# Empty_Shield_SMD-v13.net
KiCad netlist of a schematic drawn in EAGLE
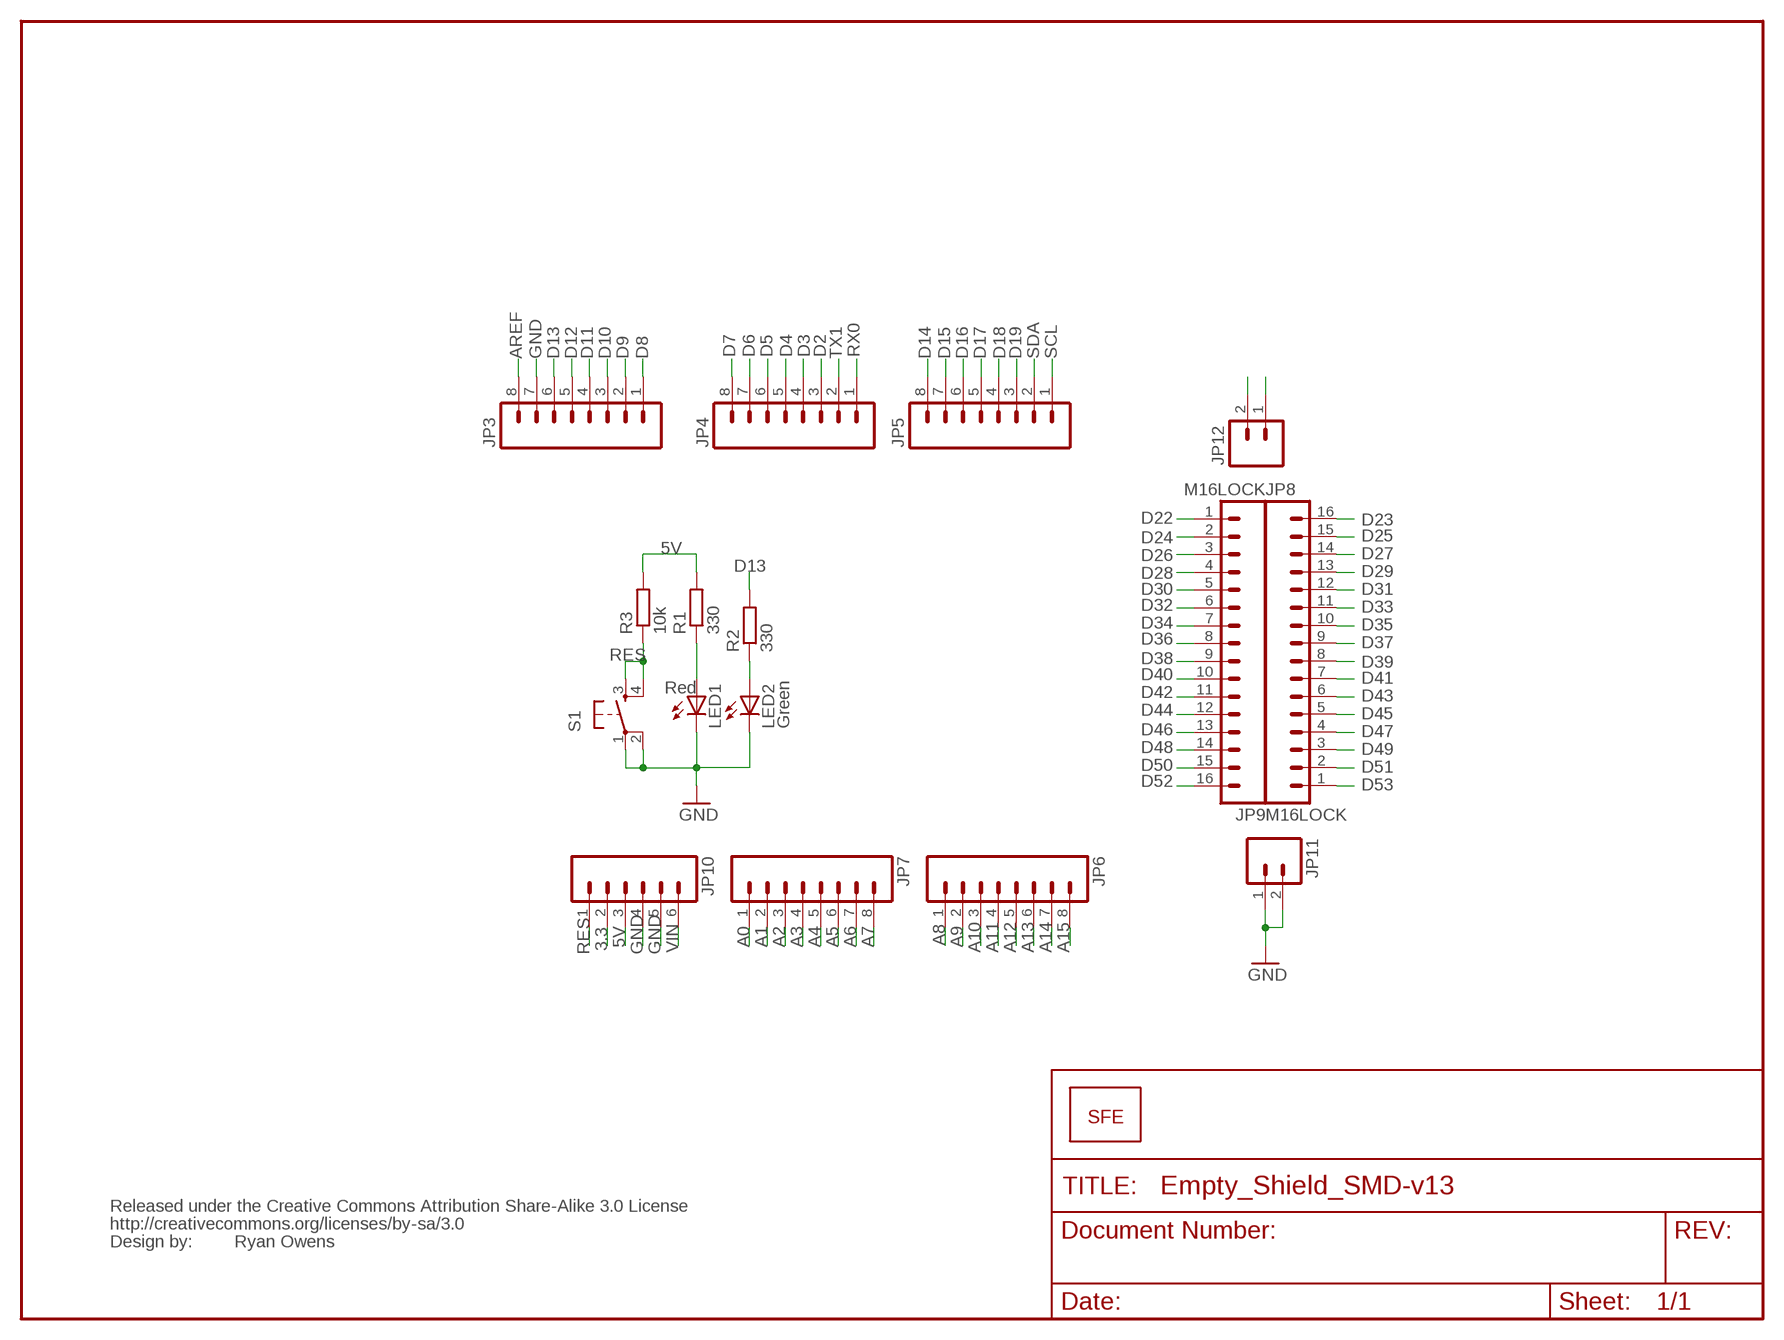
[diagram p0: schematic, sheet 1]

(export (version "E")
  (design (tool "Eeschema 10.0.6"))
  (components
    (comp (ref "JP3")
      (value "M08LOCK")
      (footprint "eagle-import:1X08_LOCK")
      (libsource (lib "eagle-import") (part "M08LOCK"))
    )
    (comp (ref "JP4")
      (value "M08LOCK")
      (footprint "eagle-import:1X08_LOCK")
      (libsource (lib "eagle-import") (part "M08LOCK"))
    )
    (comp (ref "JP5")
      (value "M08LOCK")
      (footprint "eagle-import:1X08_LOCK")
      (libsource (lib "eagle-import") (part "M08LOCK"))
    )
    (comp (ref "JP6")
      (value "M08LOCK")
      (footprint "eagle-import:1X08_LOCK")
      (libsource (lib "eagle-import") (part "M08LOCK"))
    )
    (comp (ref "JP7")
      (value "M08LOCK")
      (footprint "eagle-import:1X08_LOCK")
      (libsource (lib "eagle-import") (part "M08LOCK"))
    )
    (comp (ref "JP8")
      (value "M16LOCK")
      (footprint "eagle-import:1X16_LOCK")
      (libsource (lib "eagle-import") (part "M16LOCK"))
    )
    (comp (ref "JP9")
      (value "M16LOCK")
      (footprint "eagle-import:1X16_LOCK")
      (libsource (lib "eagle-import") (part "M16LOCK"))
    )
    (comp (ref "JP10")
      (value "M06LOCK")
      (footprint "eagle-import:1X06_LOCK")
      (libsource (lib "eagle-import") (part "M06LOCK"))
    )
    (comp (ref "JP11")
      (value "M02LOCK")
      (footprint "eagle-import:1X02_LOCK")
      (libsource (lib "eagle-import") (part "M02LOCK"))
    )
    (comp (ref "JP12")
      (value "M02LOCK")
      (footprint "eagle-import:1X02_LOCK")
      (libsource (lib "eagle-import") (part "M02LOCK"))
    )
    (comp (ref "LED1")
      (value "Red")
      (footprint "eagle-import:CHIP-LED0805")
      (libsource (lib "eagle-import") (part "LEDCHIP-LED0805"))
    )
    (comp (ref "LED2")
      (value "Green")
      (footprint "eagle-import:CHIP-LED0805")
      (libsource (lib "eagle-import") (part "LEDCHIP-LED0805"))
    )
    (comp (ref "R1")
      (value "330")
      (footprint "eagle-import:R0805")
      (libsource (lib "eagle-import") (part "R-EU_R0805"))
    )
    (comp (ref "R2")
      (value "330")
      (footprint "eagle-import:R0805")
      (libsource (lib "eagle-import") (part "R-EU_R0805"))
    )
    (comp (ref "R3")
      (value "10k")
      (footprint "eagle-import:R0805")
      (libsource (lib "eagle-import") (part "R-EU_R0805"))
    )
    (comp (ref "S1")
      (value "TAC_SWITCHPTH")
      (footprint "eagle-import:TACTILE-PTH")
      (libsource (lib "eagle-import") (part "TAC_SWITCHPTH"))
    )
    (comp (ref "U$1")
      (value "LOGO-SFENEW")
      (footprint "eagle-import:SFE-NEW-WEBLOGO")
      (libsource (lib "eagle-import") (part "LOGO-SFENEW"))
    )
    (comp (ref "U$2")
      (value "CREATIVE_COMMONS")
      (footprint "eagle-import:CREATIVE_COMMONS")
      (libsource (lib "eagle-import") (part "CREATIVE_COMMONS"))
    )
  )
  (nets
    (net (code "1") (name "/3.3") (class "Default")
      (node (ref "JP10") (pin "2") (pinfunction "2_2") (pintype "passive"))
    )
    (net (code "2") (name "/5V") (class "Default")
      (node (ref "JP10") (pin "3") (pinfunction "3_3") (pintype "passive"))
      (node (ref "R1") (pin "2") (pinfunction "2_2") (pintype "passive"))
      (node (ref "R3") (pin "2") (pinfunction "2_2") (pintype "passive"))
    )
    (net (code "3") (name "/5V@1") (class "Default")
      (node (ref "JP12") (pin "1") (pinfunction "1_1") (pintype "passive"))
      (node (ref "JP12") (pin "2") (pinfunction "2_2") (pintype "passive"))
    )
    (net (code "4") (name "/A0") (class "Default")
      (node (ref "JP7") (pin "1") (pinfunction "1_1") (pintype "passive"))
    )
    (net (code "5") (name "/A1") (class "Default")
      (node (ref "JP7") (pin "2") (pinfunction "2_2") (pintype "passive"))
    )
    (net (code "6") (name "/A2") (class "Default")
      (node (ref "JP7") (pin "3") (pinfunction "3_3") (pintype "passive"))
    )
    (net (code "7") (name "/A3") (class "Default")
      (node (ref "JP7") (pin "4") (pinfunction "4_4") (pintype "passive"))
    )
    (net (code "8") (name "/A4") (class "Default")
      (node (ref "JP7") (pin "5") (pinfunction "5_5") (pintype "passive"))
    )
    (net (code "9") (name "/A5") (class "Default")
      (node (ref "JP7") (pin "6") (pinfunction "6_6") (pintype "passive"))
    )
    (net (code "10") (name "/A6") (class "Default")
      (node (ref "JP7") (pin "7") (pinfunction "7_7") (pintype "passive"))
    )
    (net (code "11") (name "/A7") (class "Default")
      (node (ref "JP7") (pin "8") (pinfunction "8_8") (pintype "passive"))
    )
    (net (code "12") (name "/A8") (class "Default")
      (node (ref "JP6") (pin "1") (pinfunction "1_1") (pintype "passive"))
    )
    (net (code "13") (name "/A9") (class "Default")
      (node (ref "JP6") (pin "2") (pinfunction "2_2") (pintype "passive"))
    )
    (net (code "14") (name "/A10") (class "Default")
      (node (ref "JP6") (pin "3") (pinfunction "3_3") (pintype "passive"))
    )
    (net (code "15") (name "/A11") (class "Default")
      (node (ref "JP6") (pin "4") (pinfunction "4_4") (pintype "passive"))
    )
    (net (code "16") (name "/A12") (class "Default")
      (node (ref "JP6") (pin "5") (pinfunction "5_5") (pintype "passive"))
    )
    (net (code "17") (name "/A13") (class "Default")
      (node (ref "JP6") (pin "6") (pinfunction "6_6") (pintype "passive"))
    )
    (net (code "18") (name "/A14") (class "Default")
      (node (ref "JP6") (pin "7") (pinfunction "7_7") (pintype "passive"))
    )
    (net (code "19") (name "/A15") (class "Default")
      (node (ref "JP6") (pin "8") (pinfunction "8_8") (pintype "passive"))
    )
    (net (code "20") (name "/AREF") (class "Default")
      (node (ref "JP3") (pin "8") (pinfunction "8_8") (pintype "passive"))
    )
    (net (code "21") (name "/D2") (class "Default")
      (node (ref "JP4") (pin "3") (pinfunction "3_3") (pintype "passive"))
    )
    (net (code "22") (name "/D3") (class "Default")
      (node (ref "JP4") (pin "4") (pinfunction "4_4") (pintype "passive"))
    )
    (net (code "23") (name "/D4") (class "Default")
      (node (ref "JP4") (pin "5") (pinfunction "5_5") (pintype "passive"))
    )
    (net (code "24") (name "/D5") (class "Default")
      (node (ref "JP4") (pin "6") (pinfunction "6_6") (pintype "passive"))
    )
    (net (code "25") (name "/D6") (class "Default")
      (node (ref "JP4") (pin "7") (pinfunction "7_7") (pintype "passive"))
    )
    (net (code "26") (name "/D7") (class "Default")
      (node (ref "JP4") (pin "8") (pinfunction "8_8") (pintype "passive"))
    )
    (net (code "27") (name "/D8") (class "Default")
      (node (ref "JP3") (pin "1") (pinfunction "1_1") (pintype "passive"))
    )
    (net (code "28") (name "/D9") (class "Default")
      (node (ref "JP3") (pin "2") (pinfunction "2_2") (pintype "passive"))
    )
    (net (code "29") (name "/D10") (class "Default")
      (node (ref "JP3") (pin "3") (pinfunction "3_3") (pintype "passive"))
    )
    (net (code "30") (name "/D11") (class "Default")
      (node (ref "JP3") (pin "4") (pinfunction "4_4") (pintype "passive"))
    )
    (net (code "31") (name "/D12") (class "Default")
      (node (ref "JP3") (pin "5") (pinfunction "5_5") (pintype "passive"))
    )
    (net (code "32") (name "/D13") (class "Default")
      (node (ref "JP3") (pin "6") (pinfunction "6_6") (pintype "passive"))
      (node (ref "R2") (pin "2") (pinfunction "2_2") (pintype "passive"))
    )
    (net (code "33") (name "/D14") (class "Default")
      (node (ref "JP5") (pin "8") (pinfunction "8_8") (pintype "passive"))
    )
    (net (code "34") (name "/D15") (class "Default")
      (node (ref "JP5") (pin "7") (pinfunction "7_7") (pintype "passive"))
    )
    (net (code "35") (name "/D16") (class "Default")
      (node (ref "JP5") (pin "6") (pinfunction "6_6") (pintype "passive"))
    )
    (net (code "36") (name "/D17") (class "Default")
      (node (ref "JP5") (pin "5") (pinfunction "5_5") (pintype "passive"))
    )
    (net (code "37") (name "/D18") (class "Default")
      (node (ref "JP5") (pin "4") (pinfunction "4_4") (pintype "passive"))
    )
    (net (code "38") (name "/D19") (class "Default")
      (node (ref "JP5") (pin "3") (pinfunction "3_3") (pintype "passive"))
    )
    (net (code "39") (name "/D22") (class "Default")
      (node (ref "JP9") (pin "1") (pinfunction "1_1") (pintype "passive"))
    )
    (net (code "40") (name "/D23") (class "Default")
      (node (ref "JP8") (pin "16") (pinfunction "16_16") (pintype "passive"))
    )
    (net (code "41") (name "/D24") (class "Default")
      (node (ref "JP9") (pin "2") (pinfunction "2_2") (pintype "passive"))
    )
    (net (code "42") (name "/D25") (class "Default")
      (node (ref "JP8") (pin "15") (pinfunction "15_15") (pintype "passive"))
    )
    (net (code "43") (name "/D26") (class "Default")
      (node (ref "JP9") (pin "3") (pinfunction "3_3") (pintype "passive"))
    )
    (net (code "44") (name "/D27") (class "Default")
      (node (ref "JP8") (pin "14") (pinfunction "14_14") (pintype "passive"))
    )
    (net (code "45") (name "/D28") (class "Default")
      (node (ref "JP9") (pin "4") (pinfunction "4_4") (pintype "passive"))
    )
    (net (code "46") (name "/D29") (class "Default")
      (node (ref "JP8") (pin "13") (pinfunction "13_13") (pintype "passive"))
    )
    (net (code "47") (name "/D30") (class "Default")
      (node (ref "JP9") (pin "5") (pinfunction "5_5") (pintype "passive"))
    )
    (net (code "48") (name "/D31") (class "Default")
      (node (ref "JP8") (pin "12") (pinfunction "12_12") (pintype "passive"))
    )
    (net (code "49") (name "/D32") (class "Default")
      (node (ref "JP9") (pin "6") (pinfunction "6_6") (pintype "passive"))
    )
    (net (code "50") (name "/D33") (class "Default")
      (node (ref "JP8") (pin "11") (pinfunction "11_11") (pintype "passive"))
    )
    (net (code "51") (name "/D34") (class "Default")
      (node (ref "JP9") (pin "7") (pinfunction "7_7") (pintype "passive"))
    )
    (net (code "52") (name "/D35") (class "Default")
      (node (ref "JP8") (pin "10") (pinfunction "10_10") (pintype "passive"))
    )
    (net (code "53") (name "/D36") (class "Default")
      (node (ref "JP9") (pin "8") (pinfunction "8_8") (pintype "passive"))
    )
    (net (code "54") (name "/D37") (class "Default")
      (node (ref "JP8") (pin "9") (pinfunction "9_9") (pintype "passive"))
    )
    (net (code "55") (name "/D38") (class "Default")
      (node (ref "JP9") (pin "9") (pinfunction "9_9") (pintype "passive"))
    )
    (net (code "56") (name "/D39") (class "Default")
      (node (ref "JP8") (pin "8") (pinfunction "8_8") (pintype "passive"))
    )
    (net (code "57") (name "/D40") (class "Default")
      (node (ref "JP9") (pin "10") (pinfunction "10_10") (pintype "passive"))
    )
    (net (code "58") (name "/D41") (class "Default")
      (node (ref "JP8") (pin "7") (pinfunction "7_7") (pintype "passive"))
    )
    (net (code "59") (name "/D42") (class "Default")
      (node (ref "JP9") (pin "11") (pinfunction "11_11") (pintype "passive"))
    )
    (net (code "60") (name "/D43") (class "Default")
      (node (ref "JP8") (pin "6") (pinfunction "6_6") (pintype "passive"))
    )
    (net (code "61") (name "/D44") (class "Default")
      (node (ref "JP9") (pin "12") (pinfunction "12_12") (pintype "passive"))
    )
    (net (code "62") (name "/D45") (class "Default")
      (node (ref "JP8") (pin "5") (pinfunction "5_5") (pintype "passive"))
    )
    (net (code "63") (name "/D46") (class "Default")
      (node (ref "JP9") (pin "13") (pinfunction "13_13") (pintype "passive"))
    )
    (net (code "64") (name "/D47") (class "Default")
      (node (ref "JP8") (pin "4") (pinfunction "4_4") (pintype "passive"))
    )
    (net (code "65") (name "/D48") (class "Default")
      (node (ref "JP9") (pin "14") (pinfunction "14_14") (pintype "passive"))
    )
    (net (code "66") (name "/D49") (class "Default")
      (node (ref "JP8") (pin "3") (pinfunction "3_3") (pintype "passive"))
    )
    (net (code "67") (name "/D50") (class "Default")
      (node (ref "JP9") (pin "15") (pinfunction "15_15") (pintype "passive"))
    )
    (net (code "68") (name "/D51") (class "Default")
      (node (ref "JP8") (pin "2") (pinfunction "2_2") (pintype "passive"))
    )
    (net (code "69") (name "/D52") (class "Default")
      (node (ref "JP9") (pin "16") (pinfunction "16_16") (pintype "passive"))
    )
    (net (code "70") (name "/D53") (class "Default")
      (node (ref "JP8") (pin "1") (pinfunction "1_1") (pintype "passive"))
    )
    (net (code "71") (name "/RES") (class "Default")
      (node (ref "JP10") (pin "1") (pinfunction "1_1") (pintype "passive"))
      (node (ref "R3") (pin "1") (pinfunction "1_1") (pintype "passive"))
      (node (ref "S1") (pin "3") (pinfunction "3_3") (pintype "passive"))
      (node (ref "S1") (pin "4") (pinfunction "4_4") (pintype "passive"))
    )
    (net (code "72") (name "/RX0") (class "Default")
      (node (ref "JP4") (pin "1") (pinfunction "1_1") (pintype "passive"))
    )
    (net (code "73") (name "/SCL") (class "Default")
      (node (ref "JP5") (pin "1") (pinfunction "1_1") (pintype "passive"))
    )
    (net (code "74") (name "/SDA") (class "Default")
      (node (ref "JP5") (pin "2") (pinfunction "2_2") (pintype "passive"))
    )
    (net (code "75") (name "/TX1") (class "Default")
      (node (ref "JP4") (pin "2") (pinfunction "2_2") (pintype "passive"))
    )
    (net (code "76") (name "/VIN") (class "Default")
      (node (ref "JP10") (pin "6") (pinfunction "6_6") (pintype "passive"))
    )
    (net (code "77") (name "GND") (class "Default")
      (node (ref "JP10") (pin "4") (pinfunction "4_4") (pintype "passive"))
      (node (ref "JP10") (pin "5") (pinfunction "5_5") (pintype "passive"))
      (node (ref "JP11") (pin "1") (pinfunction "1_1") (pintype "passive"))
      (node (ref "JP11") (pin "2") (pinfunction "2_2") (pintype "passive"))
      (node (ref "JP3") (pin "7") (pinfunction "7_7") (pintype "passive"))
      (node (ref "LED1") (pin "C") (pinfunction "C_C") (pintype "passive"))
      (node (ref "LED2") (pin "C") (pinfunction "C_C") (pintype "passive"))
      (node (ref "S1") (pin "1") (pinfunction "1_1") (pintype "passive"))
      (node (ref "S1") (pin "2") (pinfunction "2_2") (pintype "passive"))
    )
    (net (code "78") (name "Net-(LED1-PadA)") (class "Default")
      (node (ref "LED1") (pin "A") (pinfunction "A_A") (pintype "passive"))
      (node (ref "R1") (pin "1") (pinfunction "1_1") (pintype "passive"))
    )
    (net (code "79") (name "Net-(LED2-PadA)") (class "Default")
      (node (ref "LED2") (pin "A") (pinfunction "A_A") (pintype "passive"))
      (node (ref "R2") (pin "1") (pinfunction "1_1") (pintype "passive"))
    )
  )
)
